# SCH_EDR_Project_2023-04-14.net
KiCad netlist of a schematic drawn in EasyEDA
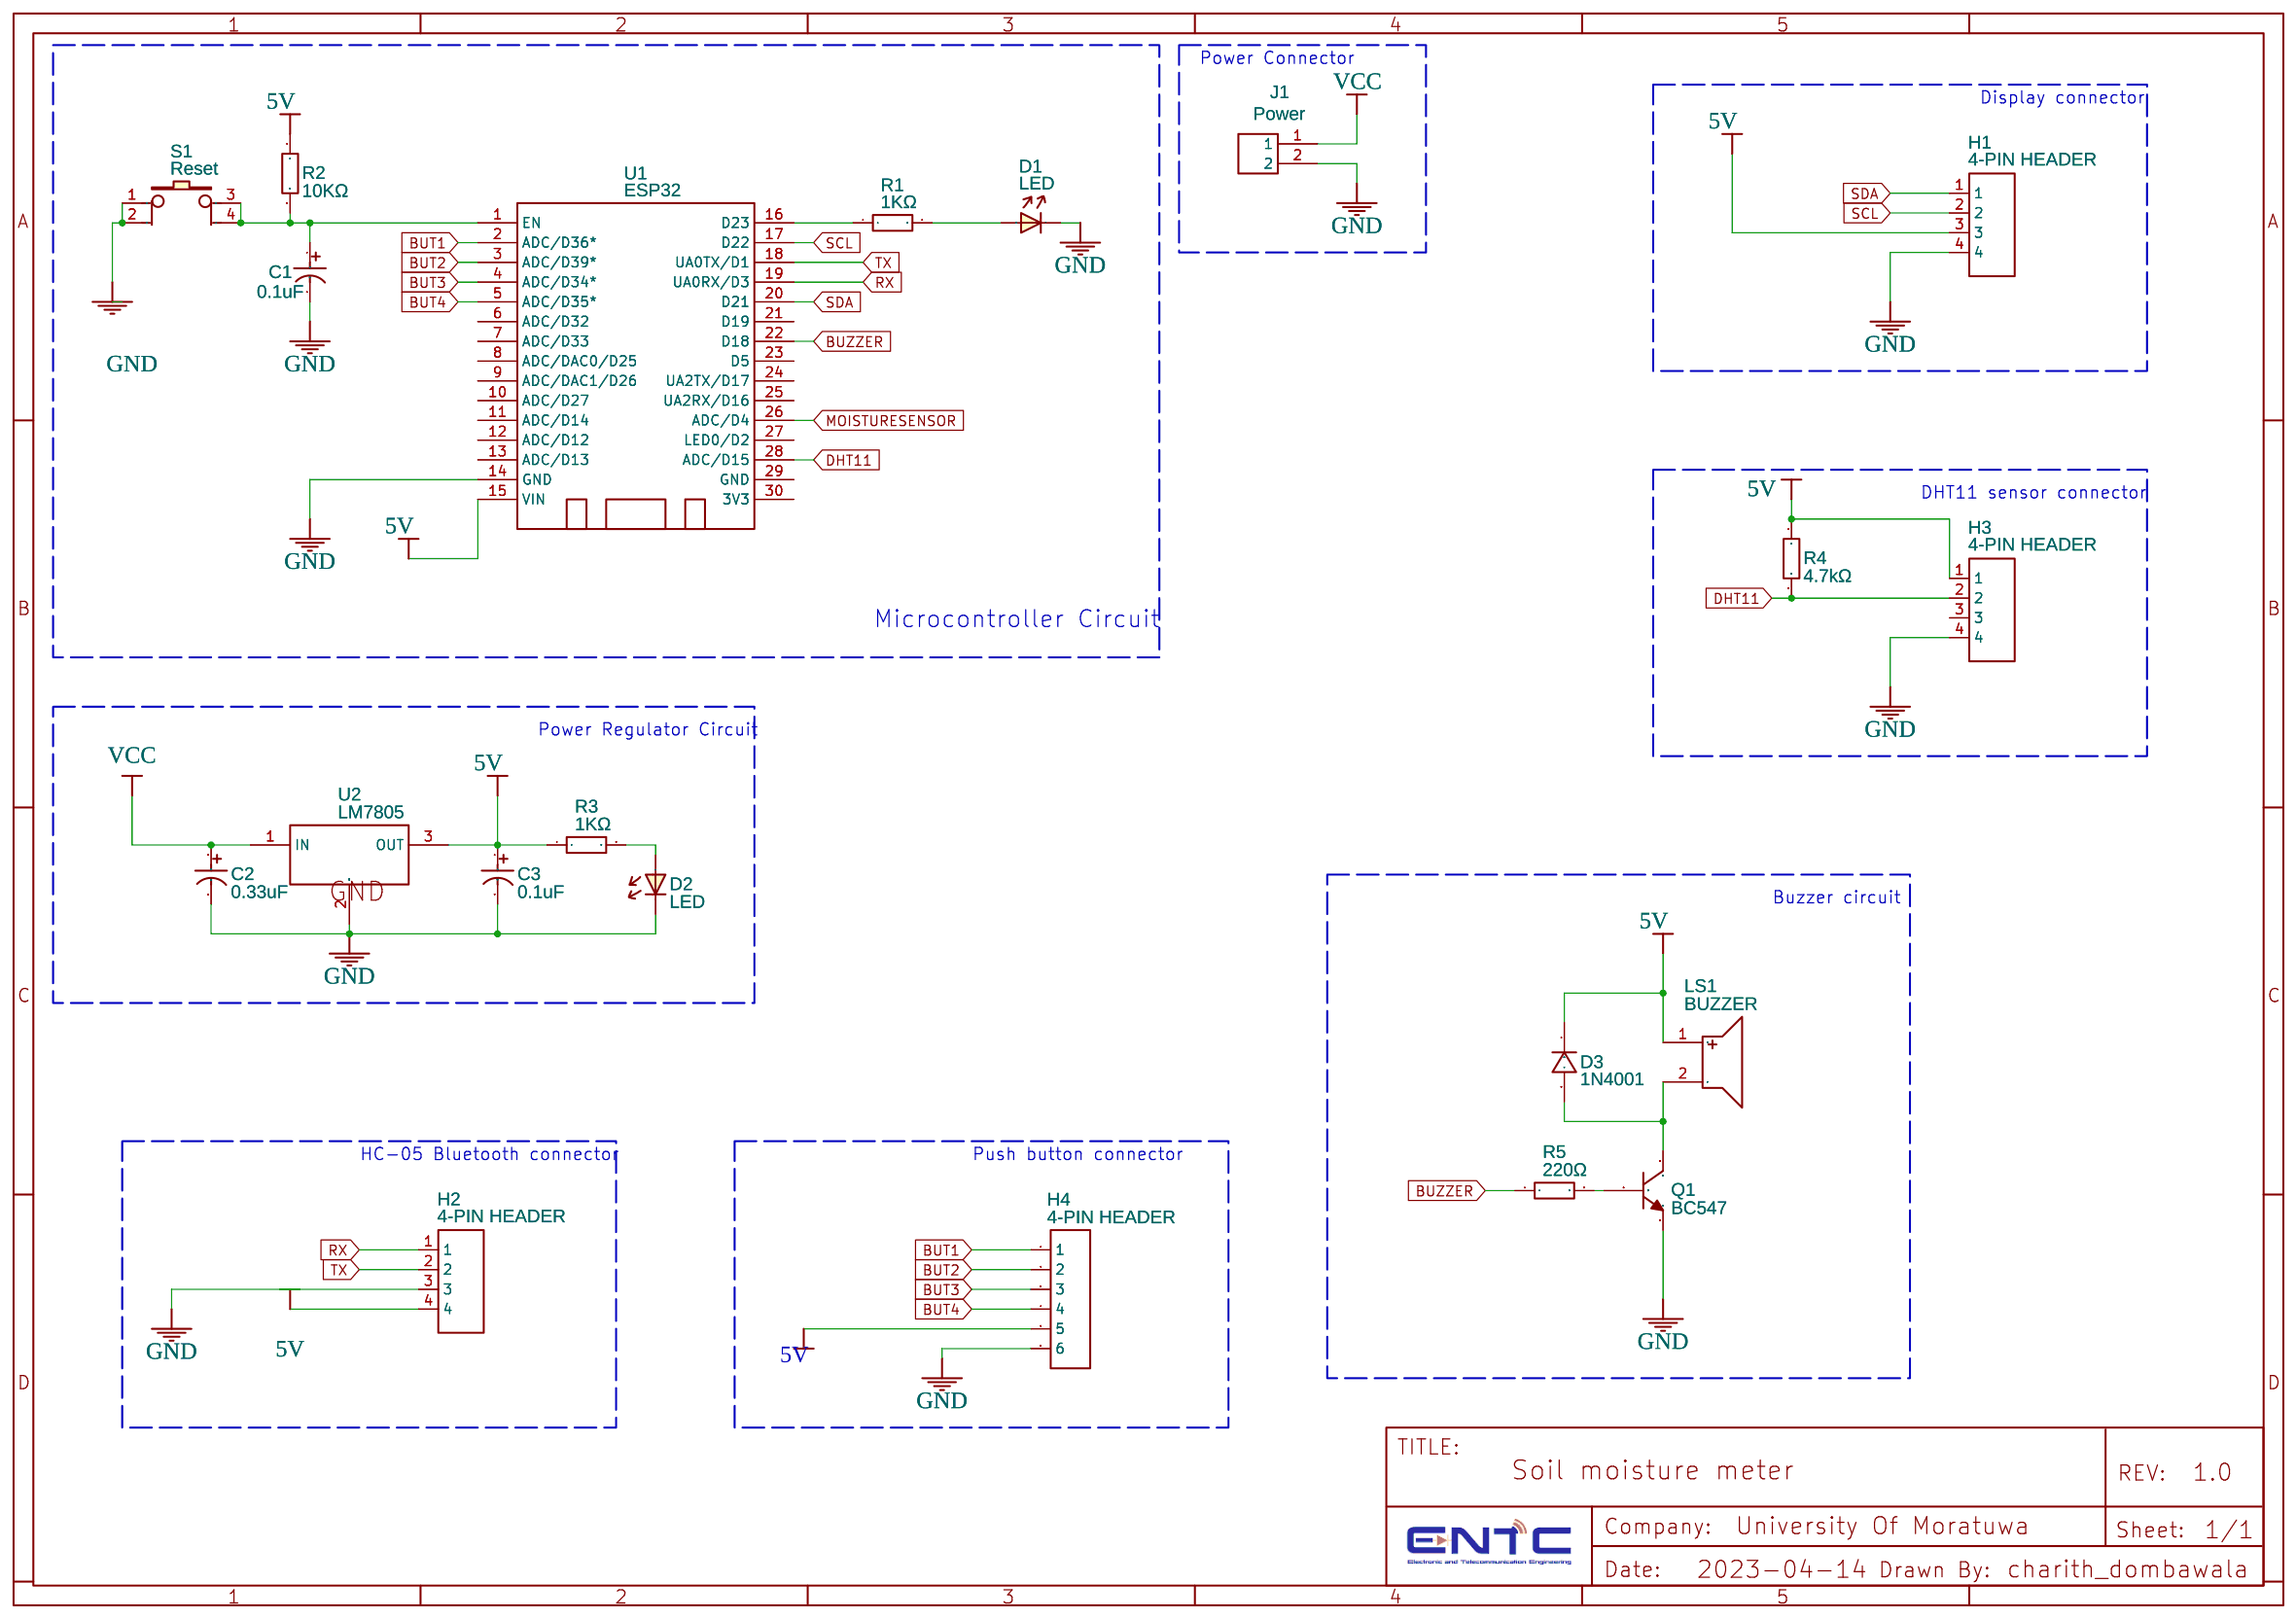
[diagram p0: schematic sheet]

(export (version "E")
  (design (tool "Eeschema 10.0.6"))
  (components
    (comp (ref "C1")
      (value "0.1uF")
      (fields (field (name "BOM_Manufacturer Part") "0.1UF 50V") (field (name "BOM_Supplier Part") "C28061"))
      (libsource (lib "") (part "0.1uF"))
    )
    (comp (ref "C2")
      (value "0.33uF")
      (fields
        (field (name "BOM_Manufacturer Part") "0.33uF 50V 5*11")
        (field (name "BOM_Supplier Part") "C45097")
      )
      (libsource (lib "") (part "0.33uF"))
    )
    (comp (ref "C3")
      (value "0.1uF")
      (fields (field (name "BOM_Manufacturer Part") "0.1UF 50V") (field (name "BOM_Supplier Part") "C28061"))
      (libsource (lib "") (part "0.1uF"))
    )
    (comp (ref "D1")
      (value "LED")
      (fields (field (name "Manufacturer Part") "5mm LED"))
      (libsource (lib "") (part "LED_1"))
    )
    (comp (ref "D2")
      (value "LED")
      (fields (field (name "Manufacturer Part") "5mm LED"))
      (libsource (lib "") (part "LED"))
    )
    (comp (ref "D3")
      (value "1N4001")
      (fields (field (name "BOM_Supplier Part") "C99656"))
      (libsource (lib "") (part "1N4001"))
    )
    (comp (ref "H1") (value "4-PIN HEADER") (libsource (lib "") (part "HEADER - HEADER-FEMALE-2.54_1X4")))
    (comp (ref "H2") (value "4-PIN HEADER") (libsource (lib "") (part "HEADER - HEADER-FEMALE-2.54_1X4")))
    (comp (ref "H3") (value "4-PIN HEADER") (libsource (lib "") (part "HEADER - HEADER-FEMALE-2.54_1X4")))
    (comp (ref "H4")
      (value "4-PIN HEADER")
      (fields (field (name "BOM_Supplier Part") "C40877"))
      (libsource (lib "") (part "HDR-F-2.54_1x6"))
    )
    (comp (ref "J1")
      (value "Power")
      (fields
        (field (name "BOM_Manufacturer Part") "XHB-2A Connector")
        (field (name "BOM_Supplier Part") "C57981")
      )
      (libsource (lib "") (part "JST_2 PIN"))
    )
    (comp (ref "LS1")
      (value "BUZZER")
      (fields
        (field (name "BOM_Manufacturer Part") "BUZZERHMB1206-03")
        (field (name "BOM_Supplier Part") "C96101")
      )
      (libsource (lib "") (part "BUZZER"))
    )
    (comp (ref "Q1")
      (value "BC547")
      (fields (field (name "BOM_Manufacturer Part") "BC547BTF") (field (name "BOM_Supplier Part") "C900798"))
      (libsource (lib "") (part "BC547BTF"))
    )
    (comp (ref "R1")
      (value "1KΩ")
      (fields
        (field (name "BOM_Manufacturer Part") "MFR0W4F2200A50")
        (field (name "BOM_Supplier Part") "E57439")
      )
      (libsource (lib "") (part "RESISTOR"))
    )
    (comp (ref "R2")
      (value "10KΩ")
      (fields
        (field (name "BOM_Manufacturer Part") "MFR0W4F2200A50")
        (field (name "BOM_Supplier Part") "E57439")
      )
      (libsource (lib "") (part "RESISTOR_1"))
    )
    (comp (ref "R3")
      (value "1KΩ")
      (fields
        (field (name "BOM_Manufacturer Part") "MFR0W4F2200A50")
        (field (name "BOM_Supplier Part") "E57439")
      )
      (libsource (lib "") (part "RESISTOR"))
    )
    (comp (ref "R4")
      (value "4.7kΩ")
      (fields
        (field (name "BOM_Manufacturer Part") "MFR0W4F2200A50")
        (field (name "BOM_Supplier Part") "E57439")
      )
      (libsource (lib "") (part "RESISTOR_1"))
    )
    (comp (ref "R5")
      (value "220Ω")
      (fields
        (field (name "BOM_Manufacturer Part") "MFR0W4F2200A50")
        (field (name "BOM_Supplier Part") "E57439")
      )
      (libsource (lib "") (part "RESISTOR"))
    )
    (comp (ref "S1")
      (value "Reset")
      (fields
        (field (name "BOM_Manufacturer Part") "button6*6*8.5")
        (field (name "BOM_Supplier Part") "C59980")
      )
      (libsource (lib "") (part "Push_Button"))
    )
    (comp (ref "U1") (value "ESP32") (libsource (lib "") (part "MODIFIED_ESP32-DEVKIT-V1 DOIT")))
    (comp (ref "U2")
      (value "LM7805")
      (fields (field (name "BOM_Manufacturer Part") "L7805CV-DG") (field (name "BOM_Supplier Part") "C3795"))
      (libsource (lib "") (part "7805(TO-220)"))
    )
  )
  (nets
    (net (code "1") (name "5V") (class "Default")
      (node (ref "C3") (pin "1") (pinfunction "1_1") (pintype "input"))
      (node (ref "D3") (pin "1") (pinfunction "C_1") (pintype "unspecified"))
      (node (ref "H1") (pin "3") (pinfunction "3_3") (pintype "unspecified"))
      (node (ref "H2") (pin "4") (pinfunction "4_4") (pintype "unspecified"))
      (node (ref "H3") (pin "1") (pinfunction "1_1") (pintype "unspecified"))
      (node (ref "H4") (pin "5") (pinfunction "5_5") (pintype "input"))
      (node (ref "LS1") (pin "1") (pinfunction "1_1") (pintype "unspecified"))
      (node (ref "R2") (pin "1") (pinfunction "1_1") (pintype "input"))
      (node (ref "R3") (pin "1") (pinfunction "1_1") (pintype "input"))
      (node (ref "R4") (pin "1") (pinfunction "1_1") (pintype "input"))
      (node (ref "U1") (pin "15") (pinfunction "VIN_15") (pintype "input"))
      (node (ref "U2") (pin "3") (pinfunction "OUT_3") (pintype "passive"))
    )
    (net (code "2") (name "BUT1") (class "Default")
      (node (ref "H4") (pin "1") (pinfunction "1_1") (pintype "input"))
      (node (ref "U1") (pin "2") (pinfunction "ADC/D36*_2") (pintype "input"))
    )
    (net (code "3") (name "BUT2") (class "Default")
      (node (ref "H4") (pin "2") (pinfunction "2_2") (pintype "input"))
      (node (ref "U1") (pin "3") (pinfunction "ADC/D39*_3") (pintype "input"))
    )
    (net (code "4") (name "BUT3") (class "Default")
      (node (ref "H4") (pin "3") (pinfunction "3_3") (pintype "input"))
      (node (ref "U1") (pin "4") (pinfunction "ADC/D34*_4") (pintype "input"))
    )
    (net (code "5") (name "BUT4") (class "Default")
      (node (ref "H4") (pin "4") (pinfunction "4_4") (pintype "input"))
      (node (ref "U1") (pin "5") (pinfunction "ADC/D35*_5") (pintype "input"))
    )
    (net (code "6") (name "BUZZER") (class "Default")
      (node (ref "R5") (pin "1") (pinfunction "1_1") (pintype "input"))
      (node (ref "U1") (pin "22") (pinfunction "D18_22") (pintype "bidirectional"))
    )
    (net (code "7") (name "DHT11") (class "Default")
      (node (ref "H3") (pin "2") (pinfunction "2_2") (pintype "unspecified"))
      (node (ref "R4") (pin "2") (pinfunction "2_2") (pintype "input"))
      (node (ref "U1") (pin "28") (pinfunction "ADC/D15_28") (pintype "bidirectional"))
    )
    (net (code "8") (name "GND") (class "Default")
      (node (ref "C1") (pin "2") (pinfunction "2_2") (pintype "input"))
      (node (ref "C2") (pin "2") (pinfunction "2_2") (pintype "input"))
      (node (ref "C3") (pin "2") (pinfunction "2_2") (pintype "input"))
      (node (ref "D1") (pin "2") (pinfunction "2_2") (pintype "unspecified"))
      (node (ref "D2") (pin "2") (pinfunction "2_2") (pintype "unspecified"))
      (node (ref "H1") (pin "4") (pinfunction "4_4") (pintype "unspecified"))
      (node (ref "H2") (pin "3") (pinfunction "3_3") (pintype "unspecified"))
      (node (ref "H3") (pin "4") (pinfunction "4_4") (pintype "unspecified"))
      (node (ref "H4") (pin "6") (pinfunction "6_6") (pintype "input"))
      (node (ref "J1") (pin "2") (pinfunction "2_2") (pintype "unspecified"))
      (node (ref "Q1") (pin "3") (pinfunction "E_3") (pintype "unspecified"))
      (node (ref "S1") (pin "1") (pinfunction "1_1") (pintype "input"))
      (node (ref "S1") (pin "2") (pinfunction "2_2") (pintype "input"))
      (node (ref "U1") (pin "14") (pinfunction "GND_14") (pintype "bidirectional"))
      (node (ref "U2") (pin "2") (pinfunction "GND_2") (pintype "passive"))
    )
    (net (code "9") (name "MOISTURESENSOR") (class "Default")
      (node (ref "U1") (pin "26") (pinfunction "ADC/D4_26") (pintype "bidirectional"))
    )
    (net (code "10") (name "Net-(D1-Pad1)") (class "Default")
      (node (ref "D1") (pin "1") (pinfunction "1_1") (pintype "unspecified"))
      (node (ref "R1") (pin "2") (pinfunction "2_2") (pintype "input"))
    )
    (net (code "11") (name "Net-(D2-Pad1)") (class "Default")
      (node (ref "D2") (pin "1") (pinfunction "1_1") (pintype "unspecified"))
      (node (ref "R3") (pin "2") (pinfunction "2_2") (pintype "input"))
    )
    (net (code "12") (name "Net-(D3-A)") (class "Default")
      (node (ref "D3") (pin "2") (pinfunction "A_2") (pintype "unspecified"))
      (node (ref "LS1") (pin "2") (pinfunction "2_2") (pintype "unspecified"))
      (node (ref "Q1") (pin "1") (pinfunction "C_1") (pintype "unspecified"))
    )
    (net (code "13") (name "Net-(Q1-B)") (class "Default")
      (node (ref "Q1") (pin "2") (pinfunction "B_2") (pintype "unspecified"))
      (node (ref "R5") (pin "2") (pinfunction "2_2") (pintype "input"))
    )
    (net (code "14") (name "Net-(U1-D23)") (class "Default")
      (node (ref "R1") (pin "1") (pinfunction "1_1") (pintype "input"))
      (node (ref "U1") (pin "16") (pinfunction "D23_16") (pintype "bidirectional"))
    )
    (net (code "15") (name "Net-(U1-EN)") (class "Default")
      (node (ref "C1") (pin "1") (pinfunction "1_1") (pintype "input"))
      (node (ref "R2") (pin "2") (pinfunction "2_2") (pintype "input"))
      (node (ref "S1") (pin "3") (pinfunction "3_3") (pintype "input"))
      (node (ref "S1") (pin "4") (pinfunction "4_4") (pintype "input"))
      (node (ref "U1") (pin "1") (pinfunction "EN_1") (pintype "bidirectional"))
    )
    (net (code "16") (name "RX") (class "Default")
      (node (ref "H2") (pin "1") (pinfunction "1_1") (pintype "unspecified"))
      (node (ref "U1") (pin "19") (pinfunction "UA0RX/D3_19") (pintype "bidirectional"))
    )
    (net (code "17") (name "SCL") (class "Default")
      (node (ref "H1") (pin "2") (pinfunction "2_2") (pintype "unspecified"))
      (node (ref "U1") (pin "17") (pinfunction "D22_17") (pintype "bidirectional"))
    )
    (net (code "18") (name "SDA") (class "Default")
      (node (ref "H1") (pin "1") (pinfunction "1_1") (pintype "unspecified"))
      (node (ref "U1") (pin "20") (pinfunction "D21_20") (pintype "bidirectional"))
    )
    (net (code "19") (name "TX") (class "Default")
      (node (ref "H2") (pin "2") (pinfunction "2_2") (pintype "unspecified"))
      (node (ref "U1") (pin "18") (pinfunction "UA0TX/D1_18") (pintype "bidirectional"))
    )
    (net (code "20") (name "VCC") (class "Default")
      (node (ref "C2") (pin "1") (pinfunction "1_1") (pintype "input"))
      (node (ref "J1") (pin "1") (pinfunction "1_1") (pintype "unspecified"))
      (node (ref "U2") (pin "1") (pinfunction "IN_1") (pintype "passive"))
    )
    (net (code "21") (name "unconnected-(H3-Pad3)") (class "Default")
      (node (ref "H3") (pin "3") (pinfunction "3_3") (pintype "unspecified"))
    )
    (net (code "22") (name "unconnected-(U1-3V3-Pad30)") (class "Default")
      (node (ref "U1") (pin "30") (pinfunction "3V3_30") (pintype "bidirectional"))
    )
    (net (code "23") (name "unconnected-(U1-ADC{slash}D12-Pad12)") (class "Default")
      (node (ref "U1") (pin "12") (pinfunction "ADC/D12_12") (pintype "bidirectional"))
    )
    (net (code "24") (name "unconnected-(U1-ADC{slash}D13-Pad13)") (class "Default")
      (node (ref "U1") (pin "13") (pinfunction "ADC/D13_13") (pintype "bidirectional"))
    )
    (net (code "25") (name "unconnected-(U1-ADC{slash}D14-Pad11)") (class "Default")
      (node (ref "U1") (pin "11") (pinfunction "ADC/D14_11") (pintype "bidirectional"))
    )
    (net (code "26") (name "unconnected-(U1-ADC{slash}D27-Pad10)") (class "Default")
      (node (ref "U1") (pin "10") (pinfunction "ADC/D27_10") (pintype "bidirectional"))
    )
    (net (code "27") (name "unconnected-(U1-ADC{slash}D32-Pad6)") (class "Default")
      (node (ref "U1") (pin "6") (pinfunction "ADC/D32_6") (pintype "bidirectional"))
    )
    (net (code "28") (name "unconnected-(U1-ADC{slash}D33-Pad7)") (class "Default")
      (node (ref "U1") (pin "7") (pinfunction "ADC/D33_7") (pintype "bidirectional"))
    )
    (net (code "29") (name "unconnected-(U1-ADC{slash}DAC0{slash}D25-Pad8)") (class "Default")
      (node (ref "U1") (pin "8") (pinfunction "ADC/DAC0/D25_8") (pintype "bidirectional"))
    )
    (net (code "30") (name "unconnected-(U1-ADC{slash}DAC1{slash}D26-Pad9)") (class "Default")
      (node (ref "U1") (pin "9") (pinfunction "ADC/DAC1/D26_9") (pintype "bidirectional"))
    )
    (net (code "31") (name "unconnected-(U1-D5-Pad23)") (class "Default")
      (node (ref "U1") (pin "23") (pinfunction "D5_23") (pintype "bidirectional"))
    )
    (net (code "32") (name "unconnected-(U1-D19-Pad21)") (class "Default")
      (node (ref "U1") (pin "21") (pinfunction "D19_21") (pintype "bidirectional"))
    )
    (net (code "33") (name "unconnected-(U1-GND-Pad29)") (class "Default")
      (node (ref "U1") (pin "29") (pinfunction "GND_29") (pintype "bidirectional"))
    )
    (net (code "34") (name "unconnected-(U1-LED0{slash}D2-Pad27)") (class "Default")
      (node (ref "U1") (pin "27") (pinfunction "LED0/D2_27") (pintype "bidirectional"))
    )
    (net (code "35") (name "unconnected-(U1-UA2RX{slash}D16-Pad25)") (class "Default")
      (node (ref "U1") (pin "25") (pinfunction "UA2RX/D16_25") (pintype "bidirectional"))
    )
    (net (code "36") (name "unconnected-(U1-UA2TX{slash}D17-Pad24)") (class "Default")
      (node (ref "U1") (pin "24") (pinfunction "UA2TX/D17_24") (pintype "bidirectional"))
    )
  )
)
